# hw3s.net
KiCad netlist of a schematic drawn in EAGLE
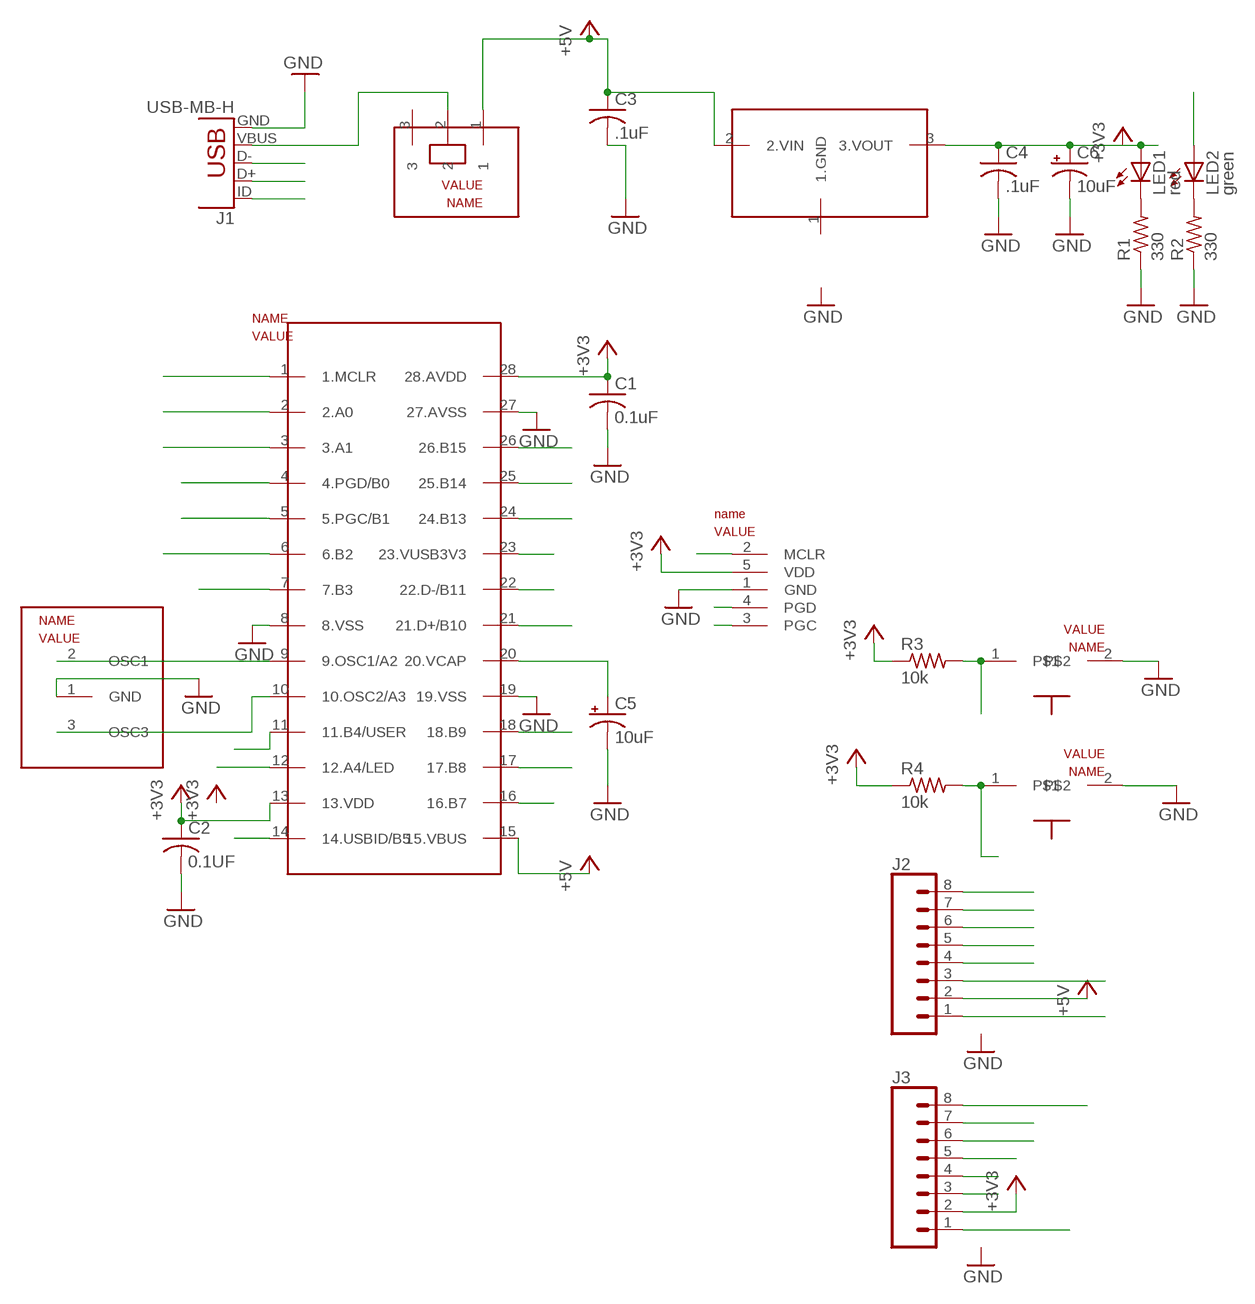
[diagram p0: schematic, sheet 1]

(export (version "E")
  (design (tool "Eeschema 10.0.6"))
  (components
    (comp (ref "C1")
      (value "0.1uF")
      (footprint "eagle-import:C025-025X050")
      (libsource (lib "eagle-import") (part "C-US025-025X050"))
    )
    (comp (ref "C2")
      (value "0.1UF")
      (footprint "eagle-import:C025-025X050")
      (libsource (lib "eagle-import") (part "C-US025-025X050"))
    )
    (comp (ref "C3")
      (value ".1uF")
      (footprint "eagle-import:C025-025X050")
      (libsource (lib "eagle-import") (part "C-US025-025X050"))
    )
    (comp (ref "C4")
      (value ".1uF")
      (footprint "eagle-import:C025-025X050")
      (libsource (lib "eagle-import") (part "C-US025-025X050"))
    )
    (comp (ref "C5")
      (value "10uF")
      (footprint "eagle-import:B45181B")
      (libsource (lib "eagle-import") (part "CPOL-USB45181B"))
    )
    (comp (ref "C6")
      (value "10uF")
      (footprint "eagle-import:B45181B")
      (libsource (lib "eagle-import") (part "CPOL-USB45181B"))
    )
    (comp (ref "J1")
      (value "USB-MB-H")
      (footprint "eagle-import:USB-MB-H")
      (libsource (lib "eagle-import") (part "USB-MB-H"))
    )
    (comp (ref "J2")
      (value "CONN_08\"")
      (footprint "eagle-import:1X08")
      (libsource (lib "eagle-import") (part "CONN_08{dblquote}"))
    )
    (comp (ref "J3")
      (value "CONN_08\"")
      (footprint "eagle-import:1X08")
      (libsource (lib "eagle-import") (part "CONN_08{dblquote}"))
    )
    (comp (ref "LED1")
      (value "red")
      (footprint "eagle-import:LED3MM")
      (libsource (lib "eagle-import") (part "LED3MM"))
    )
    (comp (ref "LED2")
      (value "green")
      (footprint "eagle-import:LED3MM")
      (libsource (lib "eagle-import") (part "LED3MM"))
    )
    (comp (ref "R1")
      (value "330")
      (footprint "eagle-import:0207_10")
      (libsource (lib "eagle-import") (part "R-US_0207/10"))
    )
    (comp (ref "R2")
      (value "330")
      (footprint "eagle-import:0207_10")
      (libsource (lib "eagle-import") (part "R-US_0207/10"))
    )
    (comp (ref "R3")
      (value "10k")
      (footprint "eagle-import:0207_10")
      (libsource (lib "eagle-import") (part "R-US_0207/10"))
    )
    (comp (ref "R4")
      (value "10k")
      (footprint "eagle-import:0207_10")
      (libsource (lib "eagle-import") (part "R-US_0207/10"))
    )
    (comp (ref "U$1")
      (value "PIC32")
      (footprint "eagle-import:DIL28-3")
      (libsource (lib "eagle-import") (part "PIC32"))
    )
    (comp (ref "U$2")
      (value "SLIDE")
      (footprint "eagle-import:SLIDE")
      (libsource (lib "eagle-import") (part "SLIDE"))
    )
    (comp (ref "U$3")
      (value "MCP1702")
      (footprint "eagle-import:TO92")
      (libsource (lib "eagle-import") (part "MCP1702"))
    )
    (comp (ref "U$4")
      (value "RESET")
      (footprint "eagle-import:PB")
      (libsource (lib "eagle-import") (part "PB"))
    )
    (comp (ref "U$5")
      (value "USER")
      (footprint "eagle-import:PB")
      (libsource (lib "eagle-import") (part "PB"))
    )
    (comp (ref "U$6")
      (value "PICKIT3")
      (footprint "eagle-import:1X05")
      (libsource (lib "eagle-import") (part "PICKIT3"))
    )
    (comp (ref "U$7")
      (value "8MHZ")
      (footprint "eagle-import:OSC")
      (libsource (lib "eagle-import") (part "OSC"))
    )
  )
  (nets
    (net (code "1") (name "+3V3") (class "Default")
      (node (ref "C1") (pin "1") (pinfunction "1_1") (pintype "passive"))
      (node (ref "C2") (pin "1") (pinfunction "1_1") (pintype "passive"))
      (node (ref "J3") (pin "2") (pinfunction "2_2") (pintype "passive"))
      (node (ref "R3") (pin "1") (pinfunction "1_1") (pintype "passive"))
      (node (ref "R4") (pin "1") (pinfunction "1_1") (pintype "passive"))
      (node (ref "U$1") (pin "13") (pinfunction "13.VDD_13") (pintype "bidirectional"))
      (node (ref "U$1") (pin "28") (pinfunction "28.AVDD_28") (pintype "bidirectional"))
      (node (ref "U$6") (pin "5") (pinfunction "VDD_5") (pintype "bidirectional"))
    )
    (net (code "2") (name "+5V") (class "Default")
      (node (ref "C3") (pin "1") (pinfunction "1_1") (pintype "passive"))
      (node (ref "J2") (pin "2") (pinfunction "2_2") (pintype "passive"))
      (node (ref "U$1") (pin "15") (pinfunction "15.VBUS_15") (pintype "bidirectional"))
      (node (ref "U$2") (pin "1") (pinfunction "1_1") (pintype "bidirectional"))
      (node (ref "U$3") (pin "2") (pinfunction "2.VIN_2") (pintype "bidirectional"))
    )
    (net (code "3") (name "/A0") (class "Default")
      (node (ref "J3") (pin "8") (pinfunction "8_8") (pintype "passive"))
      (node (ref "U$1") (pin "2") (pinfunction "2.A0_2") (pintype "bidirectional"))
    )
    (net (code "4") (name "/A1") (class "Default")
      (node (ref "J3") (pin "7") (pinfunction "7_7") (pintype "passive"))
      (node (ref "U$1") (pin "3") (pinfunction "3.A1_3") (pintype "bidirectional"))
    )
    (net (code "5") (name "/A4{slash}LED") (class "Default")
      (node (ref "J3") (pin "3") (pinfunction "3_3") (pintype "passive"))
      (node (ref "LED2") (pin "A") (pinfunction "A_A") (pintype "passive"))
      (node (ref "U$1") (pin "12") (pinfunction "12.A4/LED_12") (pintype "bidirectional"))
    )
    (net (code "6") (name "/B2") (class "Default")
      (node (ref "J3") (pin "6") (pinfunction "6_6") (pintype "passive"))
      (node (ref "U$1") (pin "6") (pinfunction "6.B2_6") (pintype "bidirectional"))
    )
    (net (code "7") (name "/B3") (class "Default")
      (node (ref "J3") (pin "5") (pinfunction "5_5") (pintype "passive"))
      (node (ref "U$1") (pin "7") (pinfunction "7.B3_7") (pintype "bidirectional"))
    )
    (net (code "8") (name "/B4{slash}USER") (class "Default")
      (node (ref "J3") (pin "4") (pinfunction "4_4") (pintype "passive"))
      (node (ref "R4") (pin "2") (pinfunction "2_2") (pintype "passive"))
      (node (ref "U$1") (pin "11") (pinfunction "11.B4/USER_11") (pintype "bidirectional"))
      (node (ref "U$5") (pin "1") (pinfunction "P$1_1") (pintype "bidirectional"))
    )
    (net (code "9") (name "/B7") (class "Default")
      (node (ref "J2") (pin "3") (pinfunction "3_3") (pintype "passive"))
      (node (ref "U$1") (pin "16") (pinfunction "16.B7_16") (pintype "bidirectional"))
    )
    (net (code "10") (name "/B8") (class "Default")
      (node (ref "J2") (pin "4") (pinfunction "4_4") (pintype "passive"))
      (node (ref "U$1") (pin "17") (pinfunction "17.B8_17") (pintype "bidirectional"))
    )
    (net (code "11") (name "/B9") (class "Default")
      (node (ref "J2") (pin "5") (pinfunction "5_5") (pintype "passive"))
      (node (ref "U$1") (pin "18") (pinfunction "18.B9_18") (pintype "bidirectional"))
    )
    (net (code "12") (name "/B13") (class "Default")
      (node (ref "J2") (pin "6") (pinfunction "6_6") (pintype "passive"))
      (node (ref "U$1") (pin "24") (pinfunction "24.B13_24") (pintype "bidirectional"))
    )
    (net (code "13") (name "/B14") (class "Default")
      (node (ref "J2") (pin "7") (pinfunction "7_7") (pintype "passive"))
      (node (ref "U$1") (pin "25") (pinfunction "25.B14_25") (pintype "bidirectional"))
    )
    (net (code "14") (name "/B15") (class "Default")
      (node (ref "J2") (pin "8") (pinfunction "8_8") (pintype "passive"))
      (node (ref "U$1") (pin "26") (pinfunction "26.B15_26") (pintype "bidirectional"))
    )
    (net (code "15") (name "/D-{slash}B11") (class "Default")
      (node (ref "J1") (pin "D-") (pinfunction "D-_D-") (pintype "bidirectional"))
      (node (ref "U$1") (pin "22") (pinfunction "22.D-/B11_22") (pintype "bidirectional"))
    )
    (net (code "16") (name "/MCLR") (class "Default")
      (node (ref "R3") (pin "2") (pinfunction "2_2") (pintype "passive"))
      (node (ref "U$1") (pin "1") (pinfunction "1.MCLR_1") (pintype "bidirectional"))
      (node (ref "U$4") (pin "1") (pinfunction "P$1_1") (pintype "bidirectional"))
      (node (ref "U$6") (pin "2") (pinfunction "MCLR_2") (pintype "bidirectional"))
    )
    (net (code "17") (name "/PGC{slash}B1") (class "Default")
      (node (ref "U$1") (pin "5") (pinfunction "5.PGC/B1_5") (pintype "bidirectional"))
      (node (ref "U$6") (pin "3") (pinfunction "PGC_3") (pintype "bidirectional"))
    )
    (net (code "18") (name "/PGD{slash}B0") (class "Default")
      (node (ref "U$1") (pin "4") (pinfunction "4.PGD/B0_4") (pintype "bidirectional"))
      (node (ref "U$6") (pin "4") (pinfunction "PGD_4") (pintype "bidirectional"))
    )
    (net (code "19") (name "/USBID{slash}B5") (class "Default")
      (node (ref "J1") (pin "ID") (pinfunction "ID_ID") (pintype "bidirectional"))
      (node (ref "U$1") (pin "14") (pinfunction "14.USBID/B5_14") (pintype "bidirectional"))
    )
    (net (code "20") (name "GND") (class "Default")
      (node (ref "C1") (pin "2") (pinfunction "2_2") (pintype "passive"))
      (node (ref "C2") (pin "2") (pinfunction "2_2") (pintype "passive"))
      (node (ref "C3") (pin "2") (pinfunction "2_2") (pintype "passive"))
      (node (ref "C4") (pin "2") (pinfunction "2_2") (pintype "passive"))
      (node (ref "C5") (pin "-") (pinfunction "-_-") (pintype "passive"))
      (node (ref "C6") (pin "-") (pinfunction "-_-") (pintype "passive"))
      (node (ref "J1") (pin "GND") (pinfunction "GND_GND") (pintype "bidirectional"))
      (node (ref "R1") (pin "1") (pinfunction "1_1") (pintype "passive"))
      (node (ref "R2") (pin "1") (pinfunction "1_1") (pintype "passive"))
      (node (ref "U$1") (pin "19") (pinfunction "19.VSS_19") (pintype "bidirectional"))
      (node (ref "U$1") (pin "27") (pinfunction "27.AVSS_27") (pintype "bidirectional"))
      (node (ref "U$1") (pin "8") (pinfunction "8.VSS_8") (pintype "bidirectional"))
      (node (ref "U$4") (pin "2") (pinfunction "P$2_2") (pintype "bidirectional"))
      (node (ref "U$5") (pin "2") (pinfunction "P$2_2") (pintype "bidirectional"))
      (node (ref "U$6") (pin "1") (pinfunction "GND_1") (pintype "bidirectional"))
      (node (ref "U$7") (pin "1") (pinfunction "GND_1") (pintype "bidirectional"))
    )
    (net (code "21") (name "Net-(J1-PadVBUS)") (class "Default")
      (node (ref "J1") (pin "VBUS") (pinfunction "VBUS_VBUS") (pintype "bidirectional"))
      (node (ref "U$2") (pin "2") (pinfunction "2_2") (pintype "bidirectional"))
    )
    (net (code "22") (name "Net-(LED1-C)") (class "Default")
      (node (ref "LED1") (pin "K") (pinfunction "C_K") (pintype "passive"))
      (node (ref "R1") (pin "2") (pinfunction "2_2") (pintype "passive"))
    )
    (net (code "23") (name "Net-(LED2-C)") (class "Default")
      (node (ref "LED2") (pin "K") (pinfunction "C_K") (pintype "passive"))
      (node (ref "R2") (pin "2") (pinfunction "2_2") (pintype "passive"))
    )
    (net (code "24") (name "Net-(U$1-9.OSC1{slash}A2)") (class "Default")
      (node (ref "U$1") (pin "9") (pinfunction "9.OSC1/A2_9") (pintype "bidirectional"))
      (node (ref "U$7") (pin "2") (pinfunction "OSC1_2") (pintype "bidirectional"))
    )
    (net (code "25") (name "Net-(U$1-10.OSC2{slash}A3)") (class "Default")
      (node (ref "U$1") (pin "10") (pinfunction "10.OSC2/A3_10") (pintype "bidirectional"))
      (node (ref "U$7") (pin "3") (pinfunction "OSC3_3") (pintype "bidirectional"))
    )
    (net (code "26") (name "Net-(U$1-20.VCAP)") (class "Default")
      (node (ref "C5") (pin "+") (pinfunction "+_+") (pintype "passive"))
      (node (ref "U$1") (pin "20") (pinfunction "20.VCAP_20") (pintype "bidirectional"))
    )
    (net (code "27") (name "Net-(U$3-3.VOUT)") (class "Default")
      (node (ref "C4") (pin "1") (pinfunction "1_1") (pintype "passive"))
      (node (ref "C6") (pin "+") (pinfunction "+_+") (pintype "passive"))
      (node (ref "LED1") (pin "A") (pinfunction "A_A") (pintype "passive"))
      (node (ref "U$3") (pin "3") (pinfunction "3.VOUT_3") (pintype "bidirectional"))
    )
    (net (code "28") (name "unconnected-(J1-PadD+)") (class "Default")
      (node (ref "J1") (pin "D+") (pinfunction "D+_D+") (pintype "bidirectional"))
    )
    (net (code "29") (name "unconnected-(J2-Pad1)") (class "Default")
      (node (ref "J2") (pin "1") (pinfunction "1_1") (pintype "passive"))
    )
    (net (code "30") (name "unconnected-(J3-Pad1)") (class "Default")
      (node (ref "J3") (pin "1") (pinfunction "1_1") (pintype "passive"))
    )
    (net (code "31") (name "unconnected-(U$1-21.D+{slash}B10-Pad21)") (class "Default")
      (node (ref "U$1") (pin "21") (pinfunction "21.D+/B10_21") (pintype "bidirectional"))
    )
    (net (code "32") (name "unconnected-(U$1-23.VUSB3V3-Pad23)") (class "Default")
      (node (ref "U$1") (pin "23") (pinfunction "23.VUSB3V3_23") (pintype "bidirectional"))
    )
    (net (code "33") (name "unconnected-(U$2-Pad3)") (class "Default")
      (node (ref "U$2") (pin "3") (pinfunction "3_3") (pintype "bidirectional"))
    )
    (net (code "34") (name "unconnected-(U$3-1.GND-Pad1)") (class "Default")
      (node (ref "U$3") (pin "1") (pinfunction "1.GND_1") (pintype "bidirectional"))
    )
  )
)
